# danger_danger_psu-mk-2.net
KiCad netlist of a schematic drawn in EAGLE
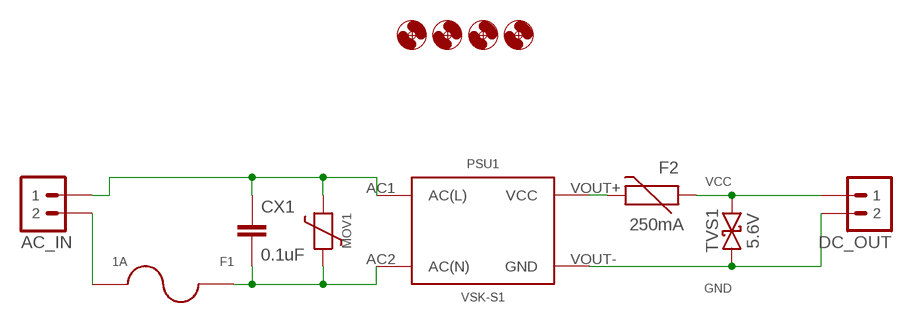
[diagram p0: schematic, sheet 1]

(export (version "E")
  (design (tool "Eeschema 10.0.6"))
  (components
    (comp (ref "AC_IN")
      (value "M023.5MM")
      (footprint "eagle-import:SCREWTERMINAL-3.5MM-2")
      (libsource (lib "eagle-import") (part "M023.5MM"))
    )
    (comp (ref "CX1")
      (value "0.1uF")
      (footprint "eagle-import:XC10B5")
      (libsource (lib "eagle-import") (part "CXXC10B5"))
    )
    (comp (ref "DC_OUT")
      (value "M02JST-PTH-VERT")
      (footprint "eagle-import:JST-2-PH-VERT-PTH")
      (libsource (lib "eagle-import") (part "M02JST-PTH-VERT"))
    )
    (comp (ref "F1")
      (value "1A")
      (footprint "eagle-import:FUSE-2AG")
      (libsource (lib "eagle-import") (part "FUSE5X20MM-2"))
    )
    (comp (ref "F2")
      (value "250mA")
      (footprint "eagle-import:PTC")
      (libsource (lib "eagle-import") (part "PTCPTH"))
    )
    (comp (ref "H1")
      (value "HOLE#2")
      (footprint "eagle-import:HOLE-#2")
      (libsource (lib "eagle-import") (part "HOLE#2"))
    )
    (comp (ref "H2")
      (value "HOLE#2")
      (footprint "eagle-import:HOLE-#2")
      (libsource (lib "eagle-import") (part "HOLE#2"))
    )
    (comp (ref "H3")
      (value "HOLE#2")
      (footprint "eagle-import:HOLE-#2")
      (libsource (lib "eagle-import") (part "HOLE#2"))
    )
    (comp (ref "H4")
      (value "HOLE#2")
      (footprint "eagle-import:HOLE-#2")
      (libsource (lib "eagle-import") (part "HOLE#2"))
    )
    (comp (ref "MOV1")
      (value "VARISITORVAR-5.08MM-PTH")
      (footprint "eagle-import:VAR-5.08MM-PTH")
      (libsource (lib "eagle-import") (part "VARISITORVAR-5.08MM-PTH"))
    )
    (comp (ref "PSU1")
      (value "VSK-S1")
      (footprint "eagle-import:VSK-S1")
      (libsource (lib "eagle-import") (part "VSK-S1"))
    )
    (comp (ref "TVS1")
      (value "5.6V")
      (footprint "eagle-import:DO-41-TVS-BI-10.16MM")
      (libsource (lib "eagle-import") (part "TVSDO-41-10.16MM"))
    )
  )
  (nets
    (net (code "1") (name "/GND") (class "Default")
      (node (ref "DC_OUT") (pin "2") (pinfunction "2_2") (pintype "passive"))
      (node (ref "PSU1") (pin "VOUT-") (pinfunction "GND_VOUT-") (pintype "bidirectional"))
      (node (ref "TVS1") (pin "P$2") (pinfunction "2_P$2") (pintype "passive"))
    )
    (net (code "2") (name "/VCC") (class "Default")
      (node (ref "DC_OUT") (pin "1") (pinfunction "1_1") (pintype "passive"))
      (node (ref "F2") (pin "P$1") (pinfunction "1_P$1") (pintype "bidirectional"))
      (node (ref "TVS1") (pin "P$1") (pinfunction "1_P$1") (pintype "passive"))
    )
    (net (code "3") (name "Net-(AC_IN-Pad2)") (class "Default")
      (node (ref "AC_IN") (pin "2") (pinfunction "2_2") (pintype "passive"))
      (node (ref "F1") (pin "2") (pinfunction "2_2") (pintype "bidirectional"))
      (node (ref "F1") (pin "2@2") (pinfunction "2_2@2") (pintype "bidirectional"))
    )
    (net (code "4") (name "Net-(F2-2)") (class "Default")
      (node (ref "F2") (pin "P$2") (pinfunction "2_P$2") (pintype "bidirectional"))
      (node (ref "PSU1") (pin "VOUT+") (pinfunction "VCC_VOUT+") (pintype "bidirectional"))
    )
    (net (code "5") (name "Net-(MOV1-P$1)") (class "Default")
      (node (ref "AC_IN") (pin "1") (pinfunction "1_1") (pintype "passive"))
      (node (ref "CX1") (pin "1") (pinfunction "1_1") (pintype "passive"))
      (node (ref "MOV1") (pin "1") (pinfunction "P$1_1") (pintype "bidirectional"))
      (node (ref "PSU1") (pin "AC1") (pinfunction "AC(L)_AC1") (pintype "bidirectional"))
    )
    (net (code "6") (name "Net-(MOV1-P$2)") (class "Default")
      (node (ref "CX1") (pin "2") (pinfunction "2_2") (pintype "passive"))
      (node (ref "F1") (pin "1") (pinfunction "1_1") (pintype "bidirectional"))
      (node (ref "F1") (pin "1@1") (pinfunction "1_1@1") (pintype "bidirectional"))
      (node (ref "MOV1") (pin "2") (pinfunction "P$2_2") (pintype "bidirectional"))
      (node (ref "PSU1") (pin "AC2") (pinfunction "AC(N)_AC2") (pintype "bidirectional"))
    )
  )
)
